# pi-shield.net
KiCad netlist of a schematic drawn in EAGLE
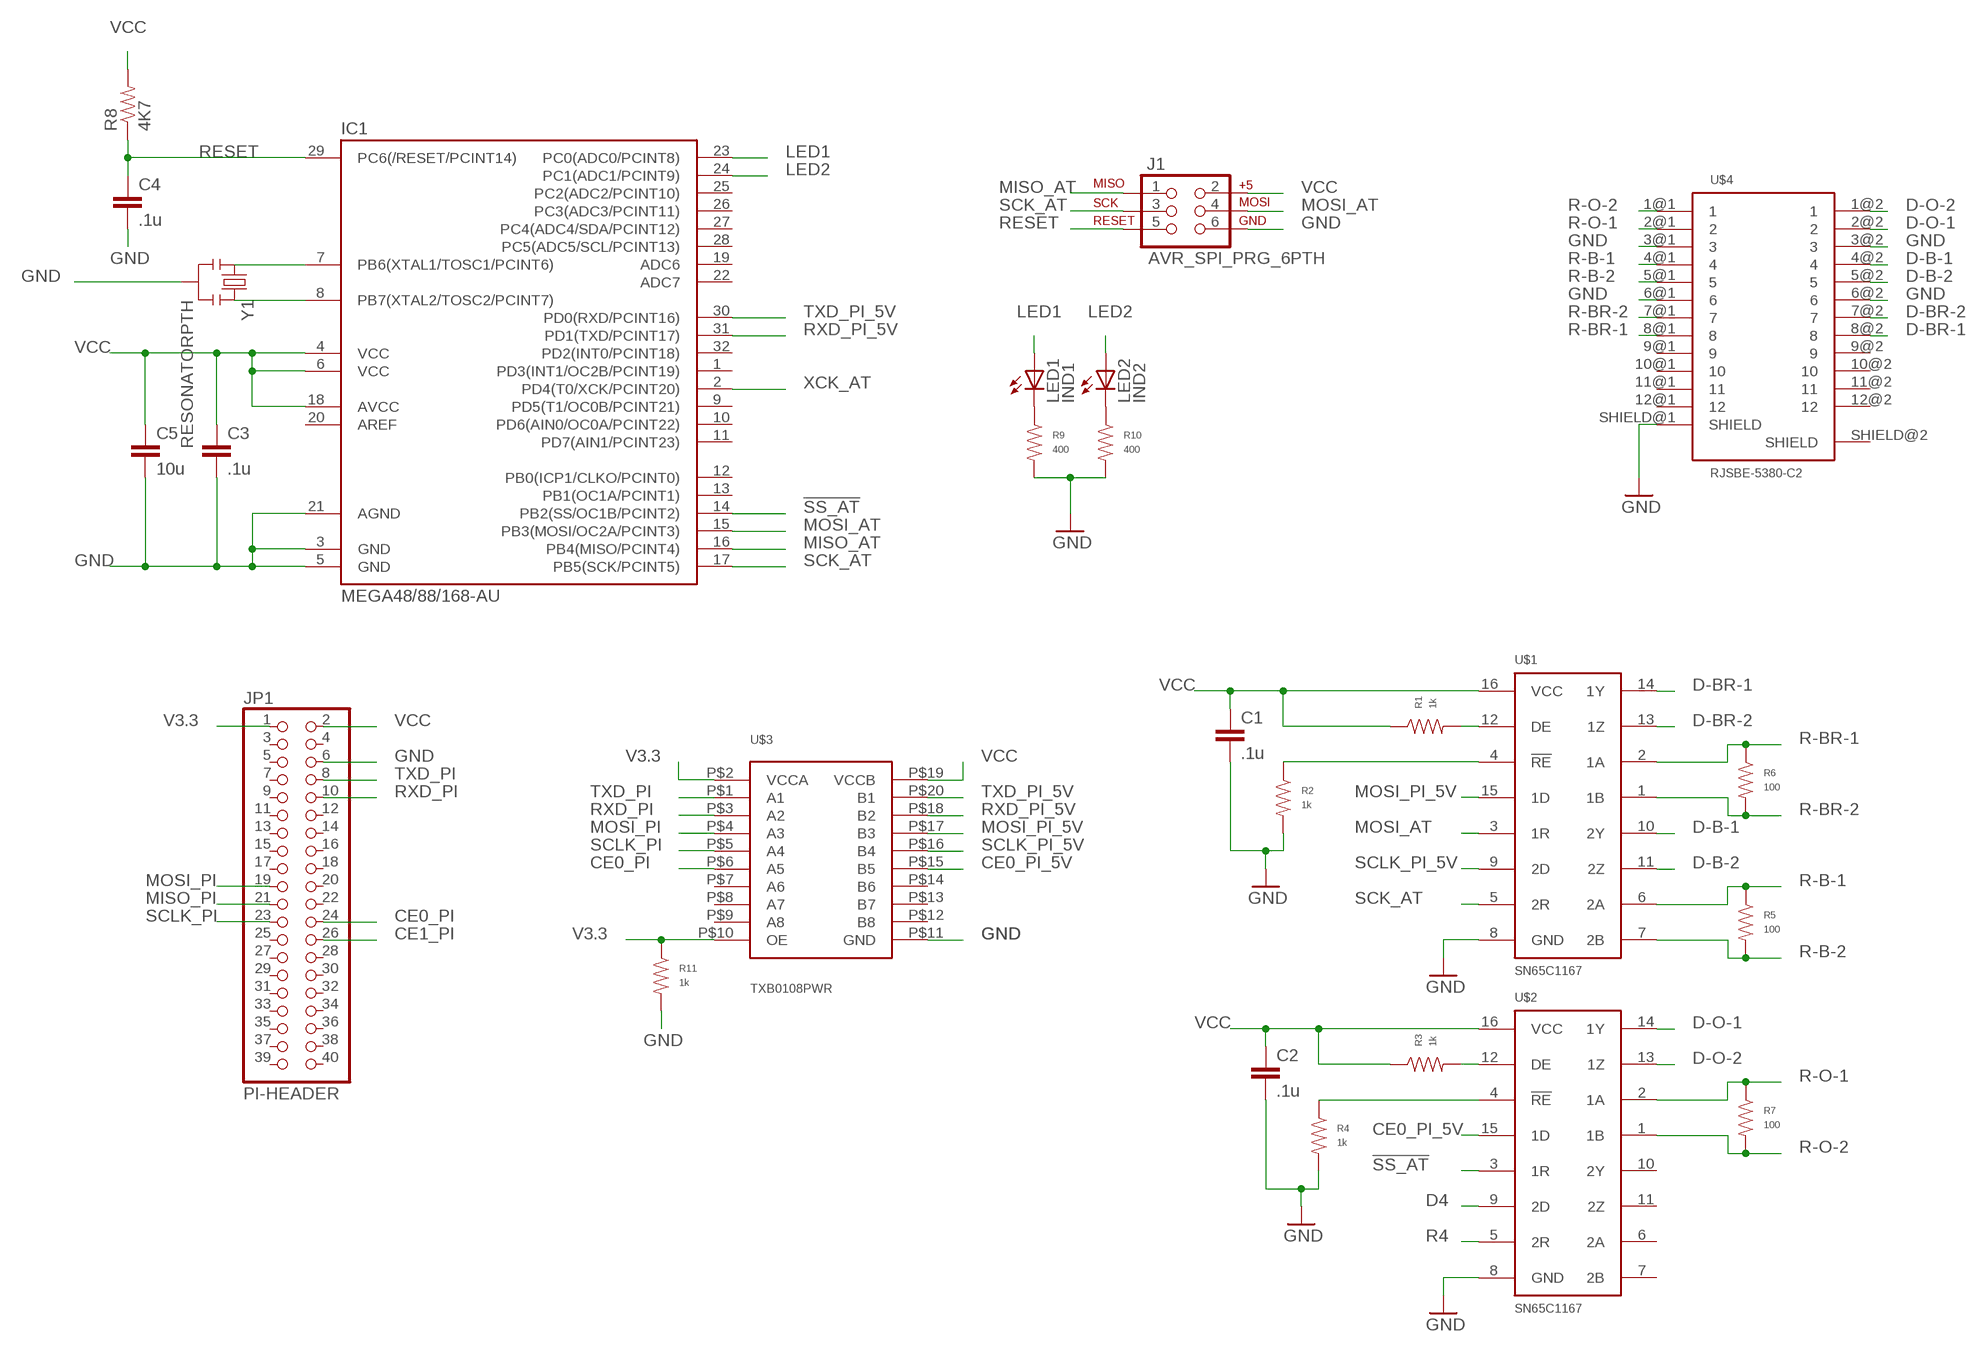
[diagram p0: schematic, sheet 1]

(export (version "E")
  (design (tool "Eeschema 10.0.6"))
  (components
    (comp (ref "C1")
      (value ".1u")
      (footprint "eagle-import:0805")
      (libsource (lib "eagle-import") (part "CAP0805"))
    )
    (comp (ref "C2")
      (value ".1u")
      (footprint "eagle-import:0805")
      (libsource (lib "eagle-import") (part "CAP0805"))
    )
    (comp (ref "C3")
      (value ".1u")
      (footprint "eagle-import:0805")
      (libsource (lib "eagle-import") (part "CAP0805"))
    )
    (comp (ref "C4")
      (value ".1u")
      (footprint "eagle-import:0805")
      (libsource (lib "eagle-import") (part "CAP0805"))
    )
    (comp (ref "C5")
      (value "10u")
      (footprint "eagle-import:0805")
      (libsource (lib "eagle-import") (part "CAP0805"))
    )
    (comp (ref "IC1")
      (value "MEGA48/88/168-AU")
      (footprint "eagle-import:TQFP32-08")
      (libsource (lib "eagle-import") (part "MEGA48/88/168-AU"))
    )
    (comp (ref "J1")
      (value "AVR_SPI_PRG_6PTH")
      (footprint "eagle-import:2X3")
      (libsource (lib "eagle-import") (part "AVR_SPI_PRG_6PTH"))
    )
    (comp (ref "JP1")
      (value "PI-HEADER")
      (footprint "eagle-import:2X20")
      (libsource (lib "eagle-import") (part "PINHD-2X20"))
    )
    (comp (ref "LED1")
      (value "IND1")
      (footprint "eagle-import:LED3MM")
      (libsource (lib "eagle-import") (part "LED3MM"))
    )
    (comp (ref "LED2")
      (value "IND2")
      (footprint "eagle-import:LED3MM")
      (libsource (lib "eagle-import") (part "LED3MM"))
    )
    (comp (ref "R1")
      (value "1k")
      (footprint "eagle-import:R0805")
      (libsource (lib "eagle-import") (part "RESISTOR_0805"))
    )
    (comp (ref "R2")
      (value "1k")
      (footprint "eagle-import:R0805")
      (libsource (lib "eagle-import") (part "RESISTOR_0805"))
    )
    (comp (ref "R3")
      (value "1k")
      (footprint "eagle-import:R0805")
      (libsource (lib "eagle-import") (part "RESISTOR_0805"))
    )
    (comp (ref "R4")
      (value "1k")
      (footprint "eagle-import:R0805")
      (libsource (lib "eagle-import") (part "RESISTOR_0805"))
    )
    (comp (ref "R5")
      (value "100")
      (footprint "eagle-import:R0805")
      (libsource (lib "eagle-import") (part "RESISTOR_0805"))
    )
    (comp (ref "R6")
      (value "100")
      (footprint "eagle-import:R0805")
      (libsource (lib "eagle-import") (part "RESISTOR_0805"))
    )
    (comp (ref "R7")
      (value "100")
      (footprint "eagle-import:R0805")
      (libsource (lib "eagle-import") (part "RESISTOR_0805"))
    )
    (comp (ref "R8")
      (value "4K7")
      (footprint "eagle-import:0805")
      (libsource (lib "eagle-import") (part "RESISTOR"))
    )
    (comp (ref "R9")
      (value "400")
      (footprint "eagle-import:R0805")
      (libsource (lib "eagle-import") (part "RESISTOR_0805"))
    )
    (comp (ref "R10")
      (value "400")
      (footprint "eagle-import:R0805")
      (libsource (lib "eagle-import") (part "RESISTOR_0805"))
    )
    (comp (ref "R11")
      (value "1k")
      (footprint "eagle-import:R0805")
      (libsource (lib "eagle-import") (part "RESISTOR_0805"))
    )
    (comp (ref "U$1")
      (value "SN65C1167")
      (footprint "eagle-import:SOP-16")
      (libsource (lib "eagle-import") (part "SN65C1167"))
    )
    (comp (ref "U$2")
      (value "SN65C1167")
      (footprint "eagle-import:SOP-16")
      (libsource (lib "eagle-import") (part "SN65C1167"))
    )
    (comp (ref "U$3")
      (value "TXB0108PWR")
      (footprint "eagle-import:TSSOP20")
      (libsource (lib "eagle-import") (part "TXB0108PWR"))
    )
    (comp (ref "U$4")
      (value "RJSBE-5380-C2")
      (footprint "eagle-import:RJSBE-5380-C2")
      (libsource (lib "eagle-import") (part "RJSBE-5380-C2"))
    )
    (comp (ref "Y1")
      (value "RESONATORPTH")
      (footprint "eagle-import:RESONATOR-PTH")
      (libsource (lib "eagle-import") (part "RESONATORPTH"))
    )
  )
  (nets
    (net (code "1") (name "/CE0_PI") (class "Default")
      (node (ref "JP1") (pin "24") (pinfunction "24_24") (pintype "passive"))
      (node (ref "U$3") (pin "P$6") (pinfunction "A5_P$6") (pintype "bidirectional"))
    )
    (net (code "2") (name "/CE0_PI_5V") (class "Default")
      (node (ref "U$2") (pin "15") (pinfunction "1D_15") (pintype "bidirectional"))
      (node (ref "U$3") (pin "P$15") (pinfunction "B5_P$15") (pintype "bidirectional"))
    )
    (net (code "3") (name "/CE1_PI") (class "Default")
      (node (ref "JP1") (pin "26") (pinfunction "26_26") (pintype "passive"))
    )
    (net (code "4") (name "/D-B-1") (class "Default")
      (node (ref "U$1") (pin "10") (pinfunction "2Y_10") (pintype "bidirectional"))
      (node (ref "U$4") (pin "4@2") (pinfunction "4_4@2") (pintype "bidirectional"))
    )
    (net (code "5") (name "/D-B-2") (class "Default")
      (node (ref "U$1") (pin "11") (pinfunction "2Z_11") (pintype "bidirectional"))
      (node (ref "U$4") (pin "5@2") (pinfunction "5_5@2") (pintype "bidirectional"))
    )
    (net (code "6") (name "/D-BR-1") (class "Default")
      (node (ref "U$1") (pin "14") (pinfunction "1Y_14") (pintype "bidirectional"))
      (node (ref "U$4") (pin "8@2") (pinfunction "8_8@2") (pintype "bidirectional"))
    )
    (net (code "7") (name "/D-BR-2") (class "Default")
      (node (ref "U$1") (pin "13") (pinfunction "1Z_13") (pintype "bidirectional"))
      (node (ref "U$4") (pin "7@2") (pinfunction "7_7@2") (pintype "bidirectional"))
    )
    (net (code "8") (name "/D-O-1") (class "Default")
      (node (ref "U$2") (pin "14") (pinfunction "1Y_14") (pintype "bidirectional"))
      (node (ref "U$4") (pin "2@2") (pinfunction "2_2@2") (pintype "bidirectional"))
    )
    (net (code "9") (name "/D-O-2") (class "Default")
      (node (ref "U$2") (pin "13") (pinfunction "1Z_13") (pintype "bidirectional"))
      (node (ref "U$4") (pin "1@2") (pinfunction "1_1@2") (pintype "bidirectional"))
    )
    (net (code "10") (name "/D4") (class "Default")
      (node (ref "U$2") (pin "9") (pinfunction "2D_9") (pintype "bidirectional"))
    )
    (net (code "11") (name "/LED1") (class "Default")
      (node (ref "IC1") (pin "23") (pinfunction "PC0(ADC0/PCINT8)_23") (pintype "bidirectional"))
      (node (ref "LED1") (pin "A") (pinfunction "A_A") (pintype "passive"))
    )
    (net (code "12") (name "/LED2") (class "Default")
      (node (ref "IC1") (pin "24") (pinfunction "PC1(ADC1/PCINT9)_24") (pintype "bidirectional"))
      (node (ref "LED2") (pin "A") (pinfunction "A_A") (pintype "passive"))
    )
    (net (code "13") (name "/MISO_AT") (class "Default")
      (node (ref "IC1") (pin "16") (pinfunction "PB4(MISO/PCINT4)_16") (pintype "bidirectional"))
      (node (ref "J1") (pin "1") (pinfunction "1_1") (pintype "passive"))
    )
    (net (code "14") (name "/MISO_PI") (class "Default")
      (node (ref "JP1") (pin "21") (pinfunction "21_21") (pintype "passive"))
    )
    (net (code "15") (name "/MOSI_AT") (class "Default")
      (node (ref "IC1") (pin "15") (pinfunction "PB3(MOSI/OC2A/PCINT3)_15") (pintype "bidirectional"))
      (node (ref "J1") (pin "4") (pinfunction "4_4") (pintype "passive"))
      (node (ref "U$1") (pin "3") (pinfunction "1R_3") (pintype "bidirectional"))
    )
    (net (code "16") (name "/MOSI_PI") (class "Default")
      (node (ref "JP1") (pin "19") (pinfunction "19_19") (pintype "passive"))
      (node (ref "U$3") (pin "P$4") (pinfunction "A3_P$4") (pintype "bidirectional"))
    )
    (net (code "17") (name "/MOSI_PI_5V") (class "Default")
      (node (ref "U$1") (pin "15") (pinfunction "1D_15") (pintype "bidirectional"))
      (node (ref "U$3") (pin "P$17") (pinfunction "B3_P$17") (pintype "bidirectional"))
    )
    (net (code "18") (name "/R-B-1") (class "Default")
      (node (ref "R5") (pin "P$1") (pinfunction "P$1_P$1") (pintype "passive"))
      (node (ref "U$1") (pin "6") (pinfunction "2A_6") (pintype "bidirectional"))
      (node (ref "U$4") (pin "4@1") (pinfunction "4_4@1") (pintype "bidirectional"))
    )
    (net (code "19") (name "/R-B-2") (class "Default")
      (node (ref "R5") (pin "P$2") (pinfunction "P$2_P$2") (pintype "passive"))
      (node (ref "U$1") (pin "7") (pinfunction "2B_7") (pintype "bidirectional"))
      (node (ref "U$4") (pin "5@1") (pinfunction "5_5@1") (pintype "bidirectional"))
    )
    (net (code "20") (name "/R-BR-1") (class "Default")
      (node (ref "R6") (pin "P$1") (pinfunction "P$1_P$1") (pintype "passive"))
      (node (ref "U$1") (pin "2") (pinfunction "1A_2") (pintype "bidirectional"))
      (node (ref "U$4") (pin "8@1") (pinfunction "8_8@1") (pintype "bidirectional"))
    )
    (net (code "21") (name "/R-BR-2") (class "Default")
      (node (ref "R6") (pin "P$2") (pinfunction "P$2_P$2") (pintype "passive"))
      (node (ref "U$1") (pin "1") (pinfunction "1B_1") (pintype "bidirectional"))
      (node (ref "U$4") (pin "7@1") (pinfunction "7_7@1") (pintype "bidirectional"))
    )
    (net (code "22") (name "/R-O-1") (class "Default")
      (node (ref "R7") (pin "P$1") (pinfunction "P$1_P$1") (pintype "passive"))
      (node (ref "U$2") (pin "2") (pinfunction "1A_2") (pintype "bidirectional"))
      (node (ref "U$4") (pin "2@1") (pinfunction "2_2@1") (pintype "bidirectional"))
    )
    (net (code "23") (name "/R-O-2") (class "Default")
      (node (ref "R7") (pin "P$2") (pinfunction "P$2_P$2") (pintype "passive"))
      (node (ref "U$2") (pin "1") (pinfunction "1B_1") (pintype "bidirectional"))
      (node (ref "U$4") (pin "1@1") (pinfunction "1_1@1") (pintype "bidirectional"))
    )
    (net (code "24") (name "/R4") (class "Default")
      (node (ref "U$2") (pin "5") (pinfunction "2R_5") (pintype "bidirectional"))
    )
    (net (code "25") (name "/RESET") (class "Default")
      (node (ref "C4") (pin "1") (pinfunction "1_1") (pintype "passive"))
      (node (ref "IC1") (pin "29") (pinfunction "PC6(/RESET/PCINT14)_29") (pintype "bidirectional"))
      (node (ref "J1") (pin "5") (pinfunction "5_5") (pintype "passive"))
      (node (ref "R8") (pin "1") (pinfunction "1_1") (pintype "passive"))
    )
    (net (code "26") (name "/RXD_PI") (class "Default")
      (node (ref "JP1") (pin "10") (pinfunction "10_10") (pintype "passive"))
      (node (ref "U$3") (pin "P$3") (pinfunction "A2_P$3") (pintype "bidirectional"))
    )
    (net (code "27") (name "/RXD_PI_5V") (class "Default")
      (node (ref "IC1") (pin "31") (pinfunction "PD1(TXD/PCINT17)_31") (pintype "bidirectional"))
      (node (ref "U$3") (pin "P$18") (pinfunction "B2_P$18") (pintype "bidirectional"))
    )
    (net (code "28") (name "/SCK_AT") (class "Default")
      (node (ref "IC1") (pin "17") (pinfunction "PB5(SCK/PCINT5)_17") (pintype "bidirectional"))
      (node (ref "J1") (pin "3") (pinfunction "3_3") (pintype "passive"))
      (node (ref "U$1") (pin "5") (pinfunction "2R_5") (pintype "bidirectional"))
    )
    (net (code "29") (name "/SCLK_PI") (class "Default")
      (node (ref "JP1") (pin "23") (pinfunction "23_23") (pintype "passive"))
      (node (ref "U$3") (pin "P$5") (pinfunction "A4_P$5") (pintype "bidirectional"))
    )
    (net (code "30") (name "/SCLK_PI_5V") (class "Default")
      (node (ref "U$1") (pin "9") (pinfunction "2D_9") (pintype "bidirectional"))
      (node (ref "U$3") (pin "P$16") (pinfunction "B4_P$16") (pintype "bidirectional"))
    )
    (net (code "31") (name "/TXD_PI") (class "Default")
      (node (ref "JP1") (pin "8") (pinfunction "8_8") (pintype "passive"))
      (node (ref "U$3") (pin "P$1") (pinfunction "A1_P$1") (pintype "bidirectional"))
    )
    (net (code "32") (name "/TXD_PI_5V") (class "Default")
      (node (ref "IC1") (pin "30") (pinfunction "PD0(RXD/PCINT16)_30") (pintype "bidirectional"))
      (node (ref "U$3") (pin "P$20") (pinfunction "B1_P$20") (pintype "bidirectional"))
    )
    (net (code "33") (name "/V3.3") (class "Default")
      (node (ref "JP1") (pin "1") (pinfunction "1_1") (pintype "passive"))
      (node (ref "R11") (pin "P$1") (pinfunction "P$1_P$1") (pintype "passive"))
      (node (ref "U$3") (pin "P$10") (pinfunction "OE_P$10") (pintype "input"))
      (node (ref "U$3") (pin "P$2") (pinfunction "VCCA_P$2") (pintype "bidirectional"))
    )
    (net (code "34") (name "/VCC") (class "Default")
      (node (ref "C1") (pin "1") (pinfunction "1_1") (pintype "passive"))
      (node (ref "C2") (pin "1") (pinfunction "1_1") (pintype "passive"))
      (node (ref "C3") (pin "1") (pinfunction "1_1") (pintype "passive"))
      (node (ref "C5") (pin "1") (pinfunction "1_1") (pintype "passive"))
      (node (ref "IC1") (pin "18") (pinfunction "AVCC_18") (pintype "passive"))
      (node (ref "IC1") (pin "4") (pinfunction "VCC_4") (pintype "power_in"))
      (node (ref "IC1") (pin "6") (pinfunction "VCC_6") (pintype "power_in"))
      (node (ref "J1") (pin "2") (pinfunction "2_2") (pintype "passive"))
      (node (ref "JP1") (pin "2") (pinfunction "2_2") (pintype "passive"))
      (node (ref "R1") (pin "P$1") (pinfunction "P$1_P$1") (pintype "passive"))
      (node (ref "R3") (pin "P$1") (pinfunction "P$1_P$1") (pintype "passive"))
      (node (ref "R8") (pin "2") (pinfunction "2_2") (pintype "passive"))
      (node (ref "U$1") (pin "16") (pinfunction "VCC_16") (pintype "bidirectional"))
      (node (ref "U$2") (pin "16") (pinfunction "VCC_16") (pintype "bidirectional"))
      (node (ref "U$3") (pin "P$19") (pinfunction "VCCB_P$19") (pintype "bidirectional"))
    )
    (net (code "35") (name "/XCK_AT") (class "Default")
      (node (ref "IC1") (pin "2") (pinfunction "PD4(T0/XCK/PCINT20)_2") (pintype "bidirectional"))
    )
    (net (code "36") (name "/~{SS_AT}") (class "Default")
      (node (ref "IC1") (pin "14") (pinfunction "PB2(SS/OC1B/PCINT2)_14") (pintype "bidirectional"))
      (node (ref "U$2") (pin "3") (pinfunction "1R_3") (pintype "bidirectional"))
    )
    (net (code "37") (name "GND") (class "Default")
      (node (ref "C1") (pin "2") (pinfunction "2_2") (pintype "passive"))
      (node (ref "C2") (pin "2") (pinfunction "2_2") (pintype "passive"))
      (node (ref "C3") (pin "2") (pinfunction "2_2") (pintype "passive"))
      (node (ref "C4") (pin "2") (pinfunction "2_2") (pintype "passive"))
      (node (ref "C5") (pin "2") (pinfunction "2_2") (pintype "passive"))
      (node (ref "IC1") (pin "21") (pinfunction "AGND_21") (pintype "power_in"))
      (node (ref "IC1") (pin "3") (pinfunction "GND_3") (pintype "power_in"))
      (node (ref "IC1") (pin "5") (pinfunction "GND_5") (pintype "power_in"))
      (node (ref "J1") (pin "6") (pinfunction "6_6") (pintype "passive"))
      (node (ref "JP1") (pin "6") (pinfunction "6_6") (pintype "passive"))
      (node (ref "R10") (pin "P$2") (pinfunction "P$2_P$2") (pintype "passive"))
      (node (ref "R11") (pin "P$2") (pinfunction "P$2_P$2") (pintype "passive"))
      (node (ref "R2") (pin "P$2") (pinfunction "P$2_P$2") (pintype "passive"))
      (node (ref "R4") (pin "P$2") (pinfunction "P$2_P$2") (pintype "passive"))
      (node (ref "R9") (pin "P$2") (pinfunction "P$2_P$2") (pintype "passive"))
      (node (ref "U$1") (pin "8") (pinfunction "GND_8") (pintype "bidirectional"))
      (node (ref "U$2") (pin "8") (pinfunction "GND_8") (pintype "bidirectional"))
      (node (ref "U$3") (pin "P$11") (pinfunction "GND_P$11") (pintype "bidirectional"))
      (node (ref "U$4") (pin "3@1") (pinfunction "3_3@1") (pintype "bidirectional"))
      (node (ref "U$4") (pin "3@2") (pinfunction "3_3@2") (pintype "bidirectional"))
      (node (ref "U$4") (pin "6@1") (pinfunction "6_6@1") (pintype "bidirectional"))
      (node (ref "U$4") (pin "6@2") (pinfunction "6_6@2") (pintype "bidirectional"))
      (node (ref "U$4") (pin "SHIELD@1") (pinfunction "SHIELD_SHIELD@1") (pintype "bidirectional"))
      (node (ref "Y1") (pin "2") (pinfunction "2_2") (pintype "passive"))
    )
    (net (code "38") (name "Net-(IC1-PB6(XTAL1{slash}TOSC1{slash}PCINT6))") (class "Default")
      (node (ref "IC1") (pin "7") (pinfunction "PB6(XTAL1/TOSC1/PCINT6)_7") (pintype "bidirectional"))
      (node (ref "Y1") (pin "1") (pinfunction "1_1") (pintype "passive"))
    )
    (net (code "39") (name "Net-(IC1-PB7(XTAL2{slash}TOSC2{slash}PCINT7))") (class "Default")
      (node (ref "IC1") (pin "8") (pinfunction "PB7(XTAL2/TOSC2/PCINT7)_8") (pintype "bidirectional"))
      (node (ref "Y1") (pin "3") (pinfunction "3_3") (pintype "passive"))
    )
    (net (code "40") (name "Net-(LED1-C)") (class "Default")
      (node (ref "LED1") (pin "K") (pinfunction "C_K") (pintype "passive"))
      (node (ref "R9") (pin "P$1") (pinfunction "P$1_P$1") (pintype "passive"))
    )
    (net (code "41") (name "Net-(LED2-C)") (class "Default")
      (node (ref "LED2") (pin "K") (pinfunction "C_K") (pintype "passive"))
      (node (ref "R10") (pin "P$1") (pinfunction "P$1_P$1") (pintype "passive"))
    )
    (net (code "42") (name "Net-(U$1-DE)") (class "Default")
      (node (ref "R1") (pin "P$2") (pinfunction "P$2_P$2") (pintype "passive"))
      (node (ref "U$1") (pin "12") (pinfunction "DE_12") (pintype "bidirectional"))
    )
    (net (code "43") (name "Net-(U$1-~{RE})") (class "Default")
      (node (ref "R2") (pin "P$1") (pinfunction "P$1_P$1") (pintype "passive"))
      (node (ref "U$1") (pin "4") (pinfunction "~{RE}_4") (pintype "bidirectional"))
    )
    (net (code "44") (name "Net-(U$2-DE)") (class "Default")
      (node (ref "R3") (pin "P$2") (pinfunction "P$2_P$2") (pintype "passive"))
      (node (ref "U$2") (pin "12") (pinfunction "DE_12") (pintype "bidirectional"))
    )
    (net (code "45") (name "Net-(U$2-~{RE})") (class "Default")
      (node (ref "R4") (pin "P$1") (pinfunction "P$1_P$1") (pintype "passive"))
      (node (ref "U$2") (pin "4") (pinfunction "~{RE}_4") (pintype "bidirectional"))
    )
    (net (code "46") (name "unconnected-(IC1-ADC6-Pad19)") (class "Default")
      (node (ref "IC1") (pin "19") (pinfunction "ADC6_19") (pintype "passive"))
    )
    (net (code "47") (name "unconnected-(IC1-ADC7-Pad22)") (class "Default")
      (node (ref "IC1") (pin "22") (pinfunction "ADC7_22") (pintype "passive"))
    )
    (net (code "48") (name "unconnected-(IC1-AREF-Pad20)") (class "Default")
      (node (ref "IC1") (pin "20") (pinfunction "AREF_20") (pintype "passive"))
    )
    (net (code "49") (name "unconnected-(IC1-PB0(ICP1{slash}CLKO{slash}PCINT0)-Pad12)") (class "Default")
      (node (ref "IC1") (pin "12") (pinfunction "PB0(ICP1/CLKO/PCINT0)_12") (pintype "bidirectional"))
    )
    (net (code "50") (name "unconnected-(IC1-PB1(OC1A{slash}PCINT1)-Pad13)") (class "Default")
      (node (ref "IC1") (pin "13") (pinfunction "PB1(OC1A/PCINT1)_13") (pintype "bidirectional"))
    )
    (net (code "51") (name "unconnected-(IC1-PC2(ADC2{slash}PCINT10)-Pad25)") (class "Default")
      (node (ref "IC1") (pin "25") (pinfunction "PC2(ADC2/PCINT10)_25") (pintype "bidirectional"))
    )
    (net (code "52") (name "unconnected-(IC1-PC3(ADC3{slash}PCINT11)-Pad26)") (class "Default")
      (node (ref "IC1") (pin "26") (pinfunction "PC3(ADC3/PCINT11)_26") (pintype "bidirectional"))
    )
    (net (code "53") (name "unconnected-(IC1-PC4(ADC4{slash}SDA{slash}PCINT12)-Pad27)") (class "Default")
      (node (ref "IC1") (pin "27") (pinfunction "PC4(ADC4/SDA/PCINT12)_27") (pintype "bidirectional"))
    )
    (net (code "54") (name "unconnected-(IC1-PC5(ADC5{slash}SCL{slash}PCINT13)-Pad28)") (class "Default")
      (node (ref "IC1") (pin "28") (pinfunction "PC5(ADC5/SCL/PCINT13)_28") (pintype "bidirectional"))
    )
    (net (code "55") (name "unconnected-(IC1-PD2(INT0{slash}PCINT18)-Pad32)") (class "Default")
      (node (ref "IC1") (pin "32") (pinfunction "PD2(INT0/PCINT18)_32") (pintype "bidirectional"))
    )
    (net (code "56") (name "unconnected-(IC1-PD3(INT1{slash}OC2B{slash}PCINT19)-Pad1)") (class "Default")
      (node (ref "IC1") (pin "1") (pinfunction "PD3(INT1/OC2B/PCINT19)_1") (pintype "bidirectional"))
    )
    (net (code "57") (name "unconnected-(IC1-PD5(T1{slash}OC0B{slash}PCINT21)-Pad9)") (class "Default")
      (node (ref "IC1") (pin "9") (pinfunction "PD5(T1/OC0B/PCINT21)_9") (pintype "bidirectional"))
    )
    (net (code "58") (name "unconnected-(IC1-PD6(AIN0{slash}OC0A{slash}PCINT22)-Pad10)") (class "Default")
      (node (ref "IC1") (pin "10") (pinfunction "PD6(AIN0/OC0A/PCINT22)_10") (pintype "bidirectional"))
    )
    (net (code "59") (name "unconnected-(IC1-PD7(AIN1{slash}PCINT23)-Pad11)") (class "Default")
      (node (ref "IC1") (pin "11") (pinfunction "PD7(AIN1/PCINT23)_11") (pintype "bidirectional"))
    )
    (net (code "60") (name "unconnected-(JP1-Pad3)") (class "Default")
      (node (ref "JP1") (pin "3") (pinfunction "3_3") (pintype "passive"))
    )
    (net (code "61") (name "unconnected-(JP1-Pad4)") (class "Default")
      (node (ref "JP1") (pin "4") (pinfunction "4_4") (pintype "passive"))
    )
    (net (code "62") (name "unconnected-(JP1-Pad5)") (class "Default")
      (node (ref "JP1") (pin "5") (pinfunction "5_5") (pintype "passive"))
    )
    (net (code "63") (name "unconnected-(JP1-Pad7)") (class "Default")
      (node (ref "JP1") (pin "7") (pinfunction "7_7") (pintype "passive"))
    )
    (net (code "64") (name "unconnected-(JP1-Pad9)") (class "Default")
      (node (ref "JP1") (pin "9") (pinfunction "9_9") (pintype "passive"))
    )
    (net (code "65") (name "unconnected-(JP1-Pad11)") (class "Default")
      (node (ref "JP1") (pin "11") (pinfunction "11_11") (pintype "passive"))
    )
    (net (code "66") (name "unconnected-(JP1-Pad12)") (class "Default")
      (node (ref "JP1") (pin "12") (pinfunction "12_12") (pintype "passive"))
    )
    (net (code "67") (name "unconnected-(JP1-Pad13)") (class "Default")
      (node (ref "JP1") (pin "13") (pinfunction "13_13") (pintype "passive"))
    )
    (net (code "68") (name "unconnected-(JP1-Pad14)") (class "Default")
      (node (ref "JP1") (pin "14") (pinfunction "14_14") (pintype "passive"))
    )
    (net (code "69") (name "unconnected-(JP1-Pad15)") (class "Default")
      (node (ref "JP1") (pin "15") (pinfunction "15_15") (pintype "passive"))
    )
    (net (code "70") (name "unconnected-(JP1-Pad16)") (class "Default")
      (node (ref "JP1") (pin "16") (pinfunction "16_16") (pintype "passive"))
    )
    (net (code "71") (name "unconnected-(JP1-Pad17)") (class "Default")
      (node (ref "JP1") (pin "17") (pinfunction "17_17") (pintype "passive"))
    )
    (net (code "72") (name "unconnected-(JP1-Pad18)") (class "Default")
      (node (ref "JP1") (pin "18") (pinfunction "18_18") (pintype "passive"))
    )
    (net (code "73") (name "unconnected-(JP1-Pad20)") (class "Default")
      (node (ref "JP1") (pin "20") (pinfunction "20_20") (pintype "passive"))
    )
    (net (code "74") (name "unconnected-(JP1-Pad22)") (class "Default")
      (node (ref "JP1") (pin "22") (pinfunction "22_22") (pintype "passive"))
    )
    (net (code "75") (name "unconnected-(JP1-Pad25)") (class "Default")
      (node (ref "JP1") (pin "25") (pinfunction "25_25") (pintype "passive"))
    )
    (net (code "76") (name "unconnected-(JP1-Pad27)") (class "Default")
      (node (ref "JP1") (pin "27") (pinfunction "27_27") (pintype "passive"))
    )
    (net (code "77") (name "unconnected-(JP1-Pad28)") (class "Default")
      (node (ref "JP1") (pin "28") (pinfunction "28_28") (pintype "passive"))
    )
    (net (code "78") (name "unconnected-(JP1-Pad29)") (class "Default")
      (node (ref "JP1") (pin "29") (pinfunction "29_29") (pintype "passive"))
    )
    (net (code "79") (name "unconnected-(JP1-Pad30)") (class "Default")
      (node (ref "JP1") (pin "30") (pinfunction "30_30") (pintype "passive"))
    )
    (net (code "80") (name "unconnected-(JP1-Pad31)") (class "Default")
      (node (ref "JP1") (pin "31") (pinfunction "31_31") (pintype "passive"))
    )
    (net (code "81") (name "unconnected-(JP1-Pad32)") (class "Default")
      (node (ref "JP1") (pin "32") (pinfunction "32_32") (pintype "passive"))
    )
    (net (code "82") (name "unconnected-(JP1-Pad33)") (class "Default")
      (node (ref "JP1") (pin "33") (pinfunction "33_33") (pintype "passive"))
    )
    (net (code "83") (name "unconnected-(JP1-Pad34)") (class "Default")
      (node (ref "JP1") (pin "34") (pinfunction "34_34") (pintype "passive"))
    )
    (net (code "84") (name "unconnected-(JP1-Pad35)") (class "Default")
      (node (ref "JP1") (pin "35") (pinfunction "35_35") (pintype "passive"))
    )
    (net (code "85") (name "unconnected-(JP1-Pad36)") (class "Default")
      (node (ref "JP1") (pin "36") (pinfunction "36_36") (pintype "passive"))
    )
    (net (code "86") (name "unconnected-(JP1-Pad37)") (class "Default")
      (node (ref "JP1") (pin "37") (pinfunction "37_37") (pintype "passive"))
    )
    (net (code "87") (name "unconnected-(JP1-Pad38)") (class "Default")
      (node (ref "JP1") (pin "38") (pinfunction "38_38") (pintype "passive"))
    )
    (net (code "88") (name "unconnected-(JP1-Pad39)") (class "Default")
      (node (ref "JP1") (pin "39") (pinfunction "39_39") (pintype "passive"))
    )
    (net (code "89") (name "unconnected-(JP1-Pad40)") (class "Default")
      (node (ref "JP1") (pin "40") (pinfunction "40_40") (pintype "passive"))
    )
    (net (code "90") (name "unconnected-(U$2-2A-Pad6)") (class "Default")
      (node (ref "U$2") (pin "6") (pinfunction "2A_6") (pintype "bidirectional"))
    )
    (net (code "91") (name "unconnected-(U$2-2B-Pad7)") (class "Default")
      (node (ref "U$2") (pin "7") (pinfunction "2B_7") (pintype "bidirectional"))
    )
    (net (code "92") (name "unconnected-(U$2-2Y-Pad10)") (class "Default")
      (node (ref "U$2") (pin "10") (pinfunction "2Y_10") (pintype "bidirectional"))
    )
    (net (code "93") (name "unconnected-(U$2-2Z-Pad11)") (class "Default")
      (node (ref "U$2") (pin "11") (pinfunction "2Z_11") (pintype "bidirectional"))
    )
    (net (code "94") (name "unconnected-(U$3-A6-PadP$7)") (class "Default")
      (node (ref "U$3") (pin "P$7") (pinfunction "A6_P$7") (pintype "bidirectional"))
    )
    (net (code "95") (name "unconnected-(U$3-A7-PadP$8)") (class "Default")
      (node (ref "U$3") (pin "P$8") (pinfunction "A7_P$8") (pintype "bidirectional"))
    )
    (net (code "96") (name "unconnected-(U$3-A8-PadP$9)") (class "Default")
      (node (ref "U$3") (pin "P$9") (pinfunction "A8_P$9") (pintype "bidirectional"))
    )
    (net (code "97") (name "unconnected-(U$3-B6-PadP$14)") (class "Default")
      (node (ref "U$3") (pin "P$14") (pinfunction "B6_P$14") (pintype "bidirectional"))
    )
    (net (code "98") (name "unconnected-(U$3-B7-PadP$13)") (class "Default")
      (node (ref "U$3") (pin "P$13") (pinfunction "B7_P$13") (pintype "bidirectional"))
    )
    (net (code "99") (name "unconnected-(U$3-B8-PadP$12)") (class "Default")
      (node (ref "U$3") (pin "P$12") (pinfunction "B8_P$12") (pintype "bidirectional"))
    )
    (net (code "100") (name "unconnected-(U$4-9-Pad9@1)") (class "Default")
      (node (ref "U$4") (pin "9@1") (pinfunction "9_9@1") (pintype "bidirectional"))
    )
    (net (code "101") (name "unconnected-(U$4-9-Pad9@2)") (class "Default")
      (node (ref "U$4") (pin "9@2") (pinfunction "9_9@2") (pintype "bidirectional"))
    )
    (net (code "102") (name "unconnected-(U$4-10-Pad10@1)") (class "Default")
      (node (ref "U$4") (pin "10@1") (pinfunction "10_10@1") (pintype "bidirectional"))
    )
    (net (code "103") (name "unconnected-(U$4-10-Pad10@2)") (class "Default")
      (node (ref "U$4") (pin "10@2") (pinfunction "10_10@2") (pintype "bidirectional"))
    )
    (net (code "104") (name "unconnected-(U$4-11-Pad11@1)") (class "Default")
      (node (ref "U$4") (pin "11@1") (pinfunction "11_11@1") (pintype "bidirectional"))
    )
    (net (code "105") (name "unconnected-(U$4-11-Pad11@2)") (class "Default")
      (node (ref "U$4") (pin "11@2") (pinfunction "11_11@2") (pintype "bidirectional"))
    )
    (net (code "106") (name "unconnected-(U$4-12-Pad12@1)") (class "Default")
      (node (ref "U$4") (pin "12@1") (pinfunction "12_12@1") (pintype "bidirectional"))
    )
    (net (code "107") (name "unconnected-(U$4-12-Pad12@2)") (class "Default")
      (node (ref "U$4") (pin "12@2") (pinfunction "12_12@2") (pintype "bidirectional"))
    )
    (net (code "108") (name "unconnected-(U$4-SHIELD-PadSHIELD@2)") (class "Default")
      (node (ref "U$4") (pin "SHIELD@2") (pinfunction "SHIELD_SHIELD@2") (pintype "bidirectional"))
    )
  )
)
